# board_componentes.net
KiCad netlist of a schematic drawn in EAGLE
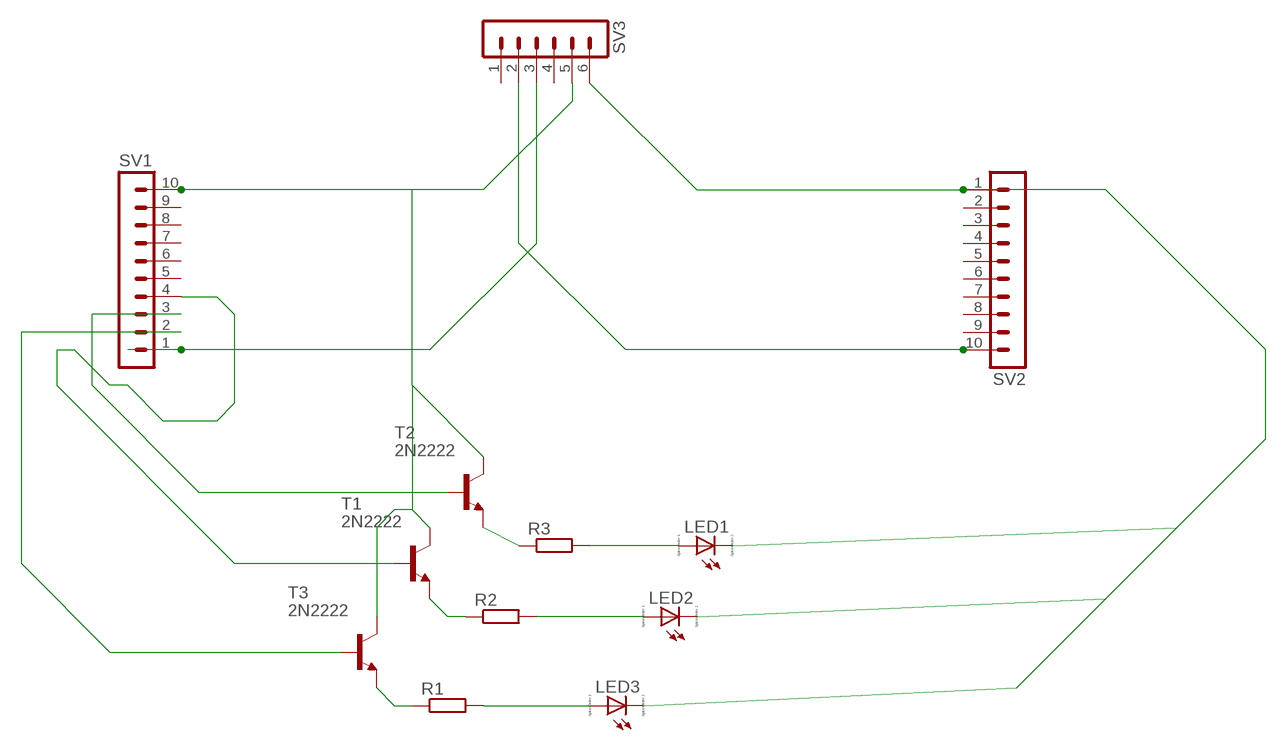
[diagram p0: schematic, sheet 1]

(export (version "E")
  (design (tool "Eeschema 10.0.6"))
  (components
    (comp (ref "LED1")
      (value "LED_ELD260")
      (footprint "eagle-import:LED_LD260")
      (libsource (lib "eagle-import") (part "LED_ELD260"))
    )
    (comp (ref "LED2")
      (value "LED_ELD260")
      (footprint "eagle-import:LED_LD260")
      (libsource (lib "eagle-import") (part "LED_ELD260"))
    )
    (comp (ref "LED3")
      (value "LED_ELD260")
      (footprint "eagle-import:LED_LD260")
      (libsource (lib "eagle-import") (part "LED_ELD260"))
    )
    (comp (ref "R1")
      (value "R-EU_0207/12")
      (footprint "eagle-import:0207_12")
      (libsource (lib "eagle-import") (part "R-EU_0207/12"))
    )
    (comp (ref "R2")
      (value "R-EU_0207/12")
      (footprint "eagle-import:0207_12")
      (libsource (lib "eagle-import") (part "R-EU_0207/12"))
    )
    (comp (ref "R3")
      (value "R-EU_0207/12")
      (footprint "eagle-import:0207_12")
      (libsource (lib "eagle-import") (part "R-EU_0207/12"))
    )
    (comp (ref "SV1")
      (value "MA10-1")
      (footprint "eagle-import:MA10-1")
      (libsource (lib "eagle-import") (part "MA10-1"))
    )
    (comp (ref "SV2")
      (value "MA10-1")
      (footprint "eagle-import:MA10-1")
      (libsource (lib "eagle-import") (part "MA10-1"))
    )
    (comp (ref "SV3")
      (value "MA06-1")
      (footprint "eagle-import:MA06-1")
      (libsource (lib "eagle-import") (part "MA06-1"))
    )
    (comp (ref "T1")
      (value "2N2222")
      (footprint "eagle-import:TO18")
      (libsource (lib "eagle-import") (part "2N2222"))
    )
    (comp (ref "T2")
      (value "2N2222")
      (footprint "eagle-import:TO18")
      (libsource (lib "eagle-import") (part "2N2222"))
    )
    (comp (ref "T3")
      (value "2N2222")
      (footprint "eagle-import:TO18")
      (libsource (lib "eagle-import") (part "2N2222"))
    )
  )
  (nets
    (net (code "1") (name "Net-(LED1-C)") (class "Default")
      (node (ref "LED1") (pin "K") (pinfunction "C_K") (pintype "passive"))
      (node (ref "LED2") (pin "K") (pinfunction "C_K") (pintype "passive"))
      (node (ref "LED3") (pin "K") (pinfunction "C_K") (pintype "passive"))
      (node (ref "SV2") (pin "1") (pinfunction "1_1") (pintype "passive"))
      (node (ref "SV3") (pin "6") (pinfunction "6_6") (pintype "passive"))
    )
    (net (code "2") (name "Net-(LED1-PadA)") (class "Default")
      (node (ref "LED1") (pin "A") (pinfunction "A_A") (pintype "passive"))
      (node (ref "R3") (pin "2") (pinfunction "2_2") (pintype "passive"))
    )
    (net (code "3") (name "Net-(LED2-PadA)") (class "Default")
      (node (ref "LED2") (pin "A") (pinfunction "A_A") (pintype "passive"))
      (node (ref "R2") (pin "2") (pinfunction "2_2") (pintype "passive"))
    )
    (net (code "4") (name "Net-(LED3-PadA)") (class "Default")
      (node (ref "LED3") (pin "A") (pinfunction "A_A") (pintype "passive"))
      (node (ref "R1") (pin "2") (pinfunction "2_2") (pintype "passive"))
    )
    (net (code "5") (name "Net-(SV1-Pad1)") (class "Default")
      (node (ref "SV1") (pin "1") (pinfunction "1_1") (pintype "passive"))
      (node (ref "SV3") (pin "3") (pinfunction "3_3") (pintype "passive"))
    )
    (net (code "6") (name "Net-(SV2-Pad10)") (class "Default")
      (node (ref "SV2") (pin "10") (pinfunction "10_10") (pintype "passive"))
      (node (ref "SV3") (pin "2") (pinfunction "2_2") (pintype "passive"))
    )
    (net (code "7") (name "Net-(T1-B)") (class "Default")
      (node (ref "SV1") (pin "4") (pinfunction "4_4") (pintype "passive"))
      (node (ref "T1") (pin "2") (pinfunction "B_2") (pintype "passive"))
    )
    (net (code "8") (name "Net-(T1-C)") (class "Default")
      (node (ref "SV1") (pin "10") (pinfunction "10_10") (pintype "passive"))
      (node (ref "SV3") (pin "5") (pinfunction "5_5") (pintype "passive"))
      (node (ref "T1") (pin "3") (pinfunction "C_3") (pintype "passive"))
      (node (ref "T2") (pin "3") (pinfunction "C_3") (pintype "passive"))
      (node (ref "T3") (pin "3") (pinfunction "C_3") (pintype "passive"))
    )
    (net (code "9") (name "Net-(T1-E)") (class "Default")
      (node (ref "R2") (pin "1") (pinfunction "1_1") (pintype "passive"))
      (node (ref "T1") (pin "1") (pinfunction "E_1") (pintype "passive"))
    )
    (net (code "10") (name "Net-(T2-B)") (class "Default")
      (node (ref "SV1") (pin "3") (pinfunction "3_3") (pintype "passive"))
      (node (ref "T2") (pin "2") (pinfunction "B_2") (pintype "passive"))
    )
    (net (code "11") (name "Net-(T2-E)") (class "Default")
      (node (ref "R3") (pin "1") (pinfunction "1_1") (pintype "passive"))
      (node (ref "T2") (pin "1") (pinfunction "E_1") (pintype "passive"))
    )
    (net (code "12") (name "Net-(T3-B)") (class "Default")
      (node (ref "SV1") (pin "2") (pinfunction "2_2") (pintype "passive"))
      (node (ref "T3") (pin "2") (pinfunction "B_2") (pintype "passive"))
    )
    (net (code "13") (name "Net-(T3-E)") (class "Default")
      (node (ref "R1") (pin "1") (pinfunction "1_1") (pintype "passive"))
      (node (ref "T3") (pin "1") (pinfunction "E_1") (pintype "passive"))
    )
    (net (code "14") (name "unconnected-(SV1-Pad5)") (class "Default")
      (node (ref "SV1") (pin "5") (pinfunction "5_5") (pintype "passive"))
    )
    (net (code "15") (name "unconnected-(SV1-Pad6)") (class "Default")
      (node (ref "SV1") (pin "6") (pinfunction "6_6") (pintype "passive"))
    )
    (net (code "16") (name "unconnected-(SV1-Pad7)") (class "Default")
      (node (ref "SV1") (pin "7") (pinfunction "7_7") (pintype "passive"))
    )
    (net (code "17") (name "unconnected-(SV1-Pad8)") (class "Default")
      (node (ref "SV1") (pin "8") (pinfunction "8_8") (pintype "passive"))
    )
    (net (code "18") (name "unconnected-(SV1-Pad9)") (class "Default")
      (node (ref "SV1") (pin "9") (pinfunction "9_9") (pintype "passive"))
    )
    (net (code "19") (name "unconnected-(SV2-Pad2)") (class "Default")
      (node (ref "SV2") (pin "2") (pinfunction "2_2") (pintype "passive"))
    )
    (net (code "20") (name "unconnected-(SV2-Pad3)") (class "Default")
      (node (ref "SV2") (pin "3") (pinfunction "3_3") (pintype "passive"))
    )
    (net (code "21") (name "unconnected-(SV2-Pad4)") (class "Default")
      (node (ref "SV2") (pin "4") (pinfunction "4_4") (pintype "passive"))
    )
    (net (code "22") (name "unconnected-(SV2-Pad5)") (class "Default")
      (node (ref "SV2") (pin "5") (pinfunction "5_5") (pintype "passive"))
    )
    (net (code "23") (name "unconnected-(SV2-Pad6)") (class "Default")
      (node (ref "SV2") (pin "6") (pinfunction "6_6") (pintype "passive"))
    )
    (net (code "24") (name "unconnected-(SV2-Pad7)") (class "Default")
      (node (ref "SV2") (pin "7") (pinfunction "7_7") (pintype "passive"))
    )
    (net (code "25") (name "unconnected-(SV2-Pad8)") (class "Default")
      (node (ref "SV2") (pin "8") (pinfunction "8_8") (pintype "passive"))
    )
    (net (code "26") (name "unconnected-(SV2-Pad9)") (class "Default")
      (node (ref "SV2") (pin "9") (pinfunction "9_9") (pintype "passive"))
    )
    (net (code "27") (name "unconnected-(SV3-Pad1)") (class "Default")
      (node (ref "SV3") (pin "1") (pinfunction "1_1") (pintype "passive"))
    )
    (net (code "28") (name "unconnected-(SV3-Pad4)") (class "Default")
      (node (ref "SV3") (pin "4") (pinfunction "4_4") (pintype "passive"))
    )
  )
)
